# MTX_Tap_an_er_V152.net
KiCad netlist of a schematic drawn in EAGLE
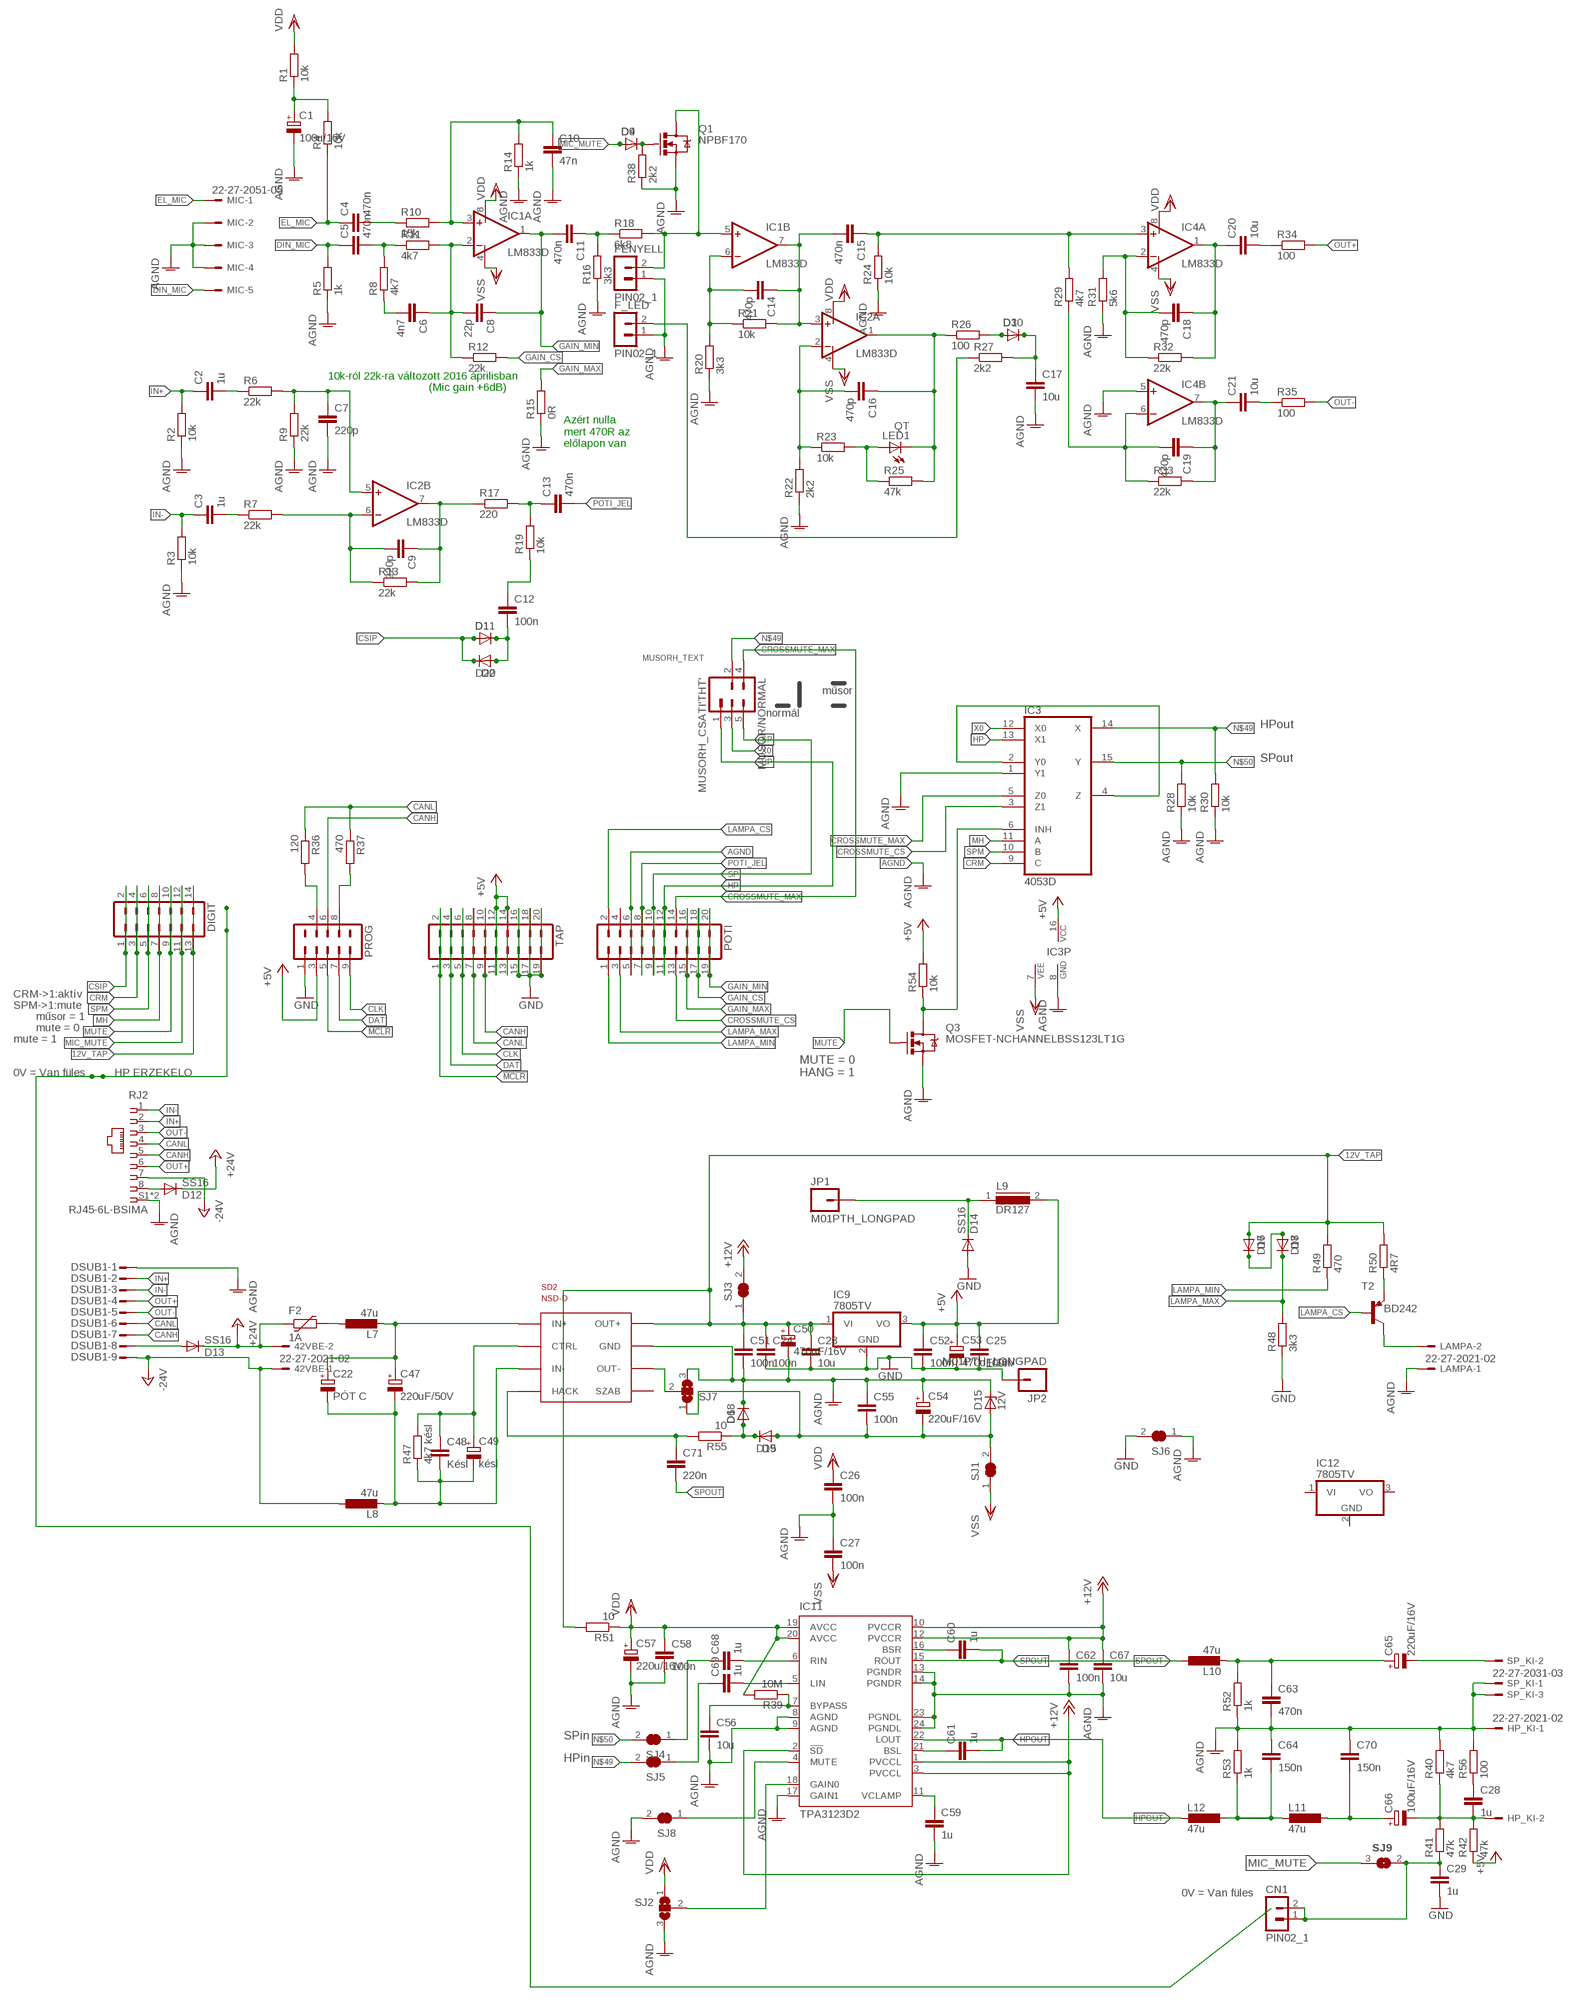
[diagram p0: schematic, sheet 1]

(export (version "E")
  (design (tool "Eeschema 10.0.6"))
  (components
    (comp (ref "42VBE")
      (value "22-27-2021-02")
      (footprint "eagle-import:6410-02")
      (libsource (lib "eagle-import") (part "22-?-0227-2021"))
    )
    (comp (ref "C1")
      (value "100u/16V")
      (footprint "eagle-import:E2,5-5")
      (libsource (lib "eagle-import") (part "CPOL-EUE2.5-5"))
    )
    (comp (ref "C2")
      (value "1u")
      (footprint "eagle-import:C0805")
      (libsource (lib "eagle-import") (part "C-EUC0805"))
    )
    (comp (ref "C3")
      (value "1u")
      (footprint "eagle-import:C0805")
      (libsource (lib "eagle-import") (part "C-EUC0805"))
    )
    (comp (ref "C4")
      (value "470n")
      (footprint "eagle-import:C0805")
      (libsource (lib "eagle-import") (part "C-EUC0805"))
    )
    (comp (ref "C5")
      (value "470n")
      (footprint "eagle-import:C0805")
      (libsource (lib "eagle-import") (part "C-EUC0805"))
    )
    (comp (ref "C6")
      (value "4n7")
      (footprint "eagle-import:C0805")
      (libsource (lib "eagle-import") (part "C-EUC0805"))
    )
    (comp (ref "C7")
      (value "220p")
      (footprint "eagle-import:C0805")
      (libsource (lib "eagle-import") (part "C-EUC0805"))
    )
    (comp (ref "C8")
      (value "22p")
      (footprint "eagle-import:C0805")
      (libsource (lib "eagle-import") (part "C-EUC0805"))
    )
    (comp (ref "C9")
      (value "220p")
      (footprint "eagle-import:C0805")
      (libsource (lib "eagle-import") (part "C-EUC0805"))
    )
    (comp (ref "C10")
      (value "47n")
      (footprint "eagle-import:C0805")
      (libsource (lib "eagle-import") (part "C-EUC0805"))
    )
    (comp (ref "C11")
      (value "470n")
      (footprint "eagle-import:C0805")
      (libsource (lib "eagle-import") (part "C-EUC0805"))
    )
    (comp (ref "C12")
      (value "100n")
      (footprint "eagle-import:C0805")
      (libsource (lib "eagle-import") (part "C-EUC0805"))
    )
    (comp (ref "C13")
      (value "470n")
      (footprint "eagle-import:C0805")
      (libsource (lib "eagle-import") (part "C-EUC0805"))
    )
    (comp (ref "C14")
      (value "470p")
      (footprint "eagle-import:C0805")
      (libsource (lib "eagle-import") (part "C-EUC0805"))
    )
    (comp (ref "C15")
      (value "470n")
      (footprint "eagle-import:C0805")
      (libsource (lib "eagle-import") (part "C-EUC0805"))
    )
    (comp (ref "C16")
      (value "470p")
      (footprint "eagle-import:C0805")
      (libsource (lib "eagle-import") (part "C-EUC0805"))
    )
    (comp (ref "C17")
      (value "10u")
      (footprint "eagle-import:C0805")
      (libsource (lib "eagle-import") (part "C-EUC0805"))
    )
    (comp (ref "C18")
      (value "470p")
      (footprint "eagle-import:C0805")
      (libsource (lib "eagle-import") (part "C-EUC0805"))
    )
    (comp (ref "C19")
      (value "470p")
      (footprint "eagle-import:C0805")
      (libsource (lib "eagle-import") (part "C-EUC0805"))
    )
    (comp (ref "C20")
      (value "10u")
      (footprint "eagle-import:C0805")
      (libsource (lib "eagle-import") (part "C-EUC0805"))
    )
    (comp (ref "C21")
      (value "10u")
      (footprint "eagle-import:C0805")
      (libsource (lib "eagle-import") (part "C-EUC0805"))
    )
    (comp (ref "C22")
      (value "PÓT C")
      (footprint "eagle-import:E3,5-8")
      (libsource (lib "eagle-import") (part "CPOL-EUE3.5-8"))
    )
    (comp (ref "C23")
      (value "10u")
      (footprint "eagle-import:C0805")
      (libsource (lib "eagle-import") (part "C-EUC0805"))
    )
    (comp (ref "C24")
      (value "100n")
      (footprint "eagle-import:C0805")
      (libsource (lib "eagle-import") (part "C-EUC0805"))
    )
    (comp (ref "C25")
      (value "100n")
      (footprint "eagle-import:C0805")
      (libsource (lib "eagle-import") (part "C-EUC0805"))
    )
    (comp (ref "C26")
      (value "100n")
      (footprint "eagle-import:C0805")
      (libsource (lib "eagle-import") (part "C-EUC0805"))
    )
    (comp (ref "C27")
      (value "100n")
      (footprint "eagle-import:C0805")
      (libsource (lib "eagle-import") (part "C-EUC0805"))
    )
    (comp (ref "C28")
      (value "1u")
      (footprint "eagle-import:C0805")
      (libsource (lib "eagle-import") (part "C-EUC0805"))
    )
    (comp (ref "C29")
      (value "1u")
      (footprint "eagle-import:C0805")
      (libsource (lib "eagle-import") (part "C-EUC0805"))
    )
    (comp (ref "C47")
      (value "220uF/50V")
      (footprint "eagle-import:E3,5-8")
      (libsource (lib "eagle-import") (part "CPOL-EUE3.5-8"))
    )
    (comp (ref "C48")
      (value "Késl")
      (footprint "eagle-import:C0805")
      (libsource (lib "eagle-import") (part "C-EUC0805"))
    )
    (comp (ref "C49")
      (value "késl")
      (footprint "eagle-import:E2,5-5")
      (libsource (lib "eagle-import") (part "CPOL-EUE2.5-5"))
    )
    (comp (ref "C50")
      (value "470uF/16V")
      (footprint "eagle-import:E3,5-8")
      (libsource (lib "eagle-import") (part "CPOL-EUE3.5-8"))
    )
    (comp (ref "C51")
      (value "100n")
      (footprint "eagle-import:C0805")
      (libsource (lib "eagle-import") (part "C-EUC0805"))
    )
    (comp (ref "C52")
      (value "100n")
      (footprint "eagle-import:C0805")
      (libsource (lib "eagle-import") (part "C-EUC0805"))
    )
    (comp (ref "C53")
      (value "470uF/16V")
      (footprint "eagle-import:E3,5-8")
      (libsource (lib "eagle-import") (part "CPOL-EUE3.5-8"))
    )
    (comp (ref "C54")
      (value "220uF/16V")
      (footprint "eagle-import:E2,5-7")
      (libsource (lib "eagle-import") (part "CPOL-EUE2.5-7"))
    )
    (comp (ref "C55")
      (value "100n")
      (footprint "eagle-import:C0805")
      (libsource (lib "eagle-import") (part "C-EUC0805"))
    )
    (comp (ref "C56")
      (value "10u")
      (footprint "eagle-import:C0805")
      (libsource (lib "eagle-import") (part "C-EUC0805"))
    )
    (comp (ref "C57")
      (value "220u/16V")
      (footprint "eagle-import:E2,5-7")
      (libsource (lib "eagle-import") (part "CPOL-EUE2.5-7"))
    )
    (comp (ref "C58")
      (value "100n")
      (footprint "eagle-import:C0805")
      (libsource (lib "eagle-import") (part "C-EUC0805"))
    )
    (comp (ref "C59")
      (value "1u")
      (footprint "eagle-import:C0805")
      (libsource (lib "eagle-import") (part "C-EUC0805"))
    )
    (comp (ref "C60")
      (value "1u")
      (footprint "eagle-import:C0805")
      (libsource (lib "eagle-import") (part "C-EUC0805"))
    )
    (comp (ref "C61")
      (value "1u")
      (footprint "eagle-import:C0805")
      (libsource (lib "eagle-import") (part "C-EUC0805"))
    )
    (comp (ref "C62")
      (value "100n")
      (footprint "eagle-import:C0805")
      (libsource (lib "eagle-import") (part "C-EUC0805"))
    )
    (comp (ref "C63")
      (value "470n")
      (footprint "eagle-import:C0805")
      (libsource (lib "eagle-import") (part "C-EUC0805"))
    )
    (comp (ref "C64")
      (value "150n")
      (footprint "eagle-import:C0805")
      (libsource (lib "eagle-import") (part "C-EUC0805"))
    )
    (comp (ref "C65")
      (value "220uF/16V")
      (footprint "eagle-import:E2,5-7")
      (libsource (lib "eagle-import") (part "CPOL-EUE2.5-7"))
    )
    (comp (ref "C66")
      (value "100uF/16V")
      (footprint "eagle-import:E2,5-6")
      (libsource (lib "eagle-import") (part "CPOL-EUE2.5-6"))
    )
    (comp (ref "C67")
      (value "10u")
      (footprint "eagle-import:C0805")
      (libsource (lib "eagle-import") (part "C-EUC0805"))
    )
    (comp (ref "C68")
      (value "1u")
      (footprint "eagle-import:C0805")
      (libsource (lib "eagle-import") (part "C-EUC0805"))
    )
    (comp (ref "C69")
      (value "1u")
      (footprint "eagle-import:C0805")
      (libsource (lib "eagle-import") (part "C-EUC0805"))
    )
    (comp (ref "C70")
      (value "150n")
      (footprint "eagle-import:C0805")
      (libsource (lib "eagle-import") (part "C-EUC0805"))
    )
    (comp (ref "C71")
      (value "220n")
      (footprint "eagle-import:C0805")
      (libsource (lib "eagle-import") (part "C-EUC0805"))
    )
    (comp (ref "CN1")
      (value "PIN02_1")
      (footprint "eagle-import:PIN02_1")
      (libsource (lib "eagle-import") (part "PIN02_1"))
    )
    (comp (ref "D1")
      (value "1N4148")
      (footprint "eagle-import:DGLASSSMD")
      (libsource (lib "eagle-import") (part "DGLASSMD"))
    )
    (comp (ref "D2")
      (value "1N4148")
      (footprint "eagle-import:DGLASSSMD")
      (libsource (lib "eagle-import") (part "DGLASSMD"))
    )
    (comp (ref "D3")
      (value "1N4148")
      (footprint "eagle-import:DGLASSSMD")
      (libsource (lib "eagle-import") (part "DGLASSMD"))
    )
    (comp (ref "D4")
      (value "1N4148")
      (footprint "eagle-import:DGLASSSMD")
      (libsource (lib "eagle-import") (part "DGLASSMD"))
    )
    (comp (ref "D5")
      (value "D0805")
      (footprint "eagle-import:D0805")
      (libsource (lib "eagle-import") (part "D0805"))
    )
    (comp (ref "D6")
      (value "D0805")
      (footprint "eagle-import:D0805")
      (libsource (lib "eagle-import") (part "D0805"))
    )
    (comp (ref "D7")
      (value "D0805")
      (footprint "eagle-import:D0805")
      (libsource (lib "eagle-import") (part "D0805"))
    )
    (comp (ref "D8")
      (value "D0805")
      (footprint "eagle-import:D0805")
      (libsource (lib "eagle-import") (part "D0805"))
    )
    (comp (ref "D9")
      (value "D0805")
      (footprint "eagle-import:D0805")
      (libsource (lib "eagle-import") (part "D0805"))
    )
    (comp (ref "D10")
      (value "D0805")
      (footprint "eagle-import:D0805")
      (libsource (lib "eagle-import") (part "D0805"))
    )
    (comp (ref "D11")
      (value "D0805")
      (footprint "eagle-import:D0805")
      (libsource (lib "eagle-import") (part "D0805"))
    )
    (comp (ref "D12")
      (value "SS16")
      (footprint "eagle-import:DO-214AC")
      (libsource (lib "eagle-import") (part "SS16"))
    )
    (comp (ref "D13")
      (value "SS16")
      (footprint "eagle-import:DO-214AC")
      (libsource (lib "eagle-import") (part "SS16"))
    )
    (comp (ref "D14")
      (value "SS16")
      (footprint "eagle-import:DO-214AC")
      (libsource (lib "eagle-import") (part "DIODE-DO-214AC"))
    )
    (comp (ref "D15")
      (value "12V")
      (footprint "eagle-import:SOD80C")
      (libsource (lib "eagle-import") (part "ZENER-DIODESOD80C"))
    )
    (comp (ref "D16")
      (value "1N4148")
      (footprint "eagle-import:DGLASSSMD")
      (libsource (lib "eagle-import") (part "DGLASSMD"))
    )
    (comp (ref "D17")
      (value "1N4148")
      (footprint "eagle-import:DGLASSSMD")
      (libsource (lib "eagle-import") (part "DGLASSMD"))
    )
    (comp (ref "D18")
      (value "1N4148")
      (footprint "eagle-import:DGLASSSMD")
      (libsource (lib "eagle-import") (part "DGLASSMD"))
    )
    (comp (ref "D19")
      (value "1N4148")
      (footprint "eagle-import:DGLASSSMD")
      (libsource (lib "eagle-import") (part "DGLASSMD"))
    )
    (comp (ref "D20")
      (value "D0805")
      (footprint "eagle-import:D0805")
      (libsource (lib "eagle-import") (part "D0805"))
    )
    (comp (ref "DIGIT")
      (value "MA07-2")
      (footprint "eagle-import:MA07-2")
      (libsource (lib "eagle-import") (part "MA07-2"))
    )
    (comp (ref "DSUB1")
      (value "M09-182S")
      (footprint "eagle-import:182-009-MALE")
      (libsource (lib "eagle-import") (part "M09?S-182"))
    )
    (comp (ref "F2")
      (value "1A")
      (footprint "eagle-import:PTC1812L")
      (libsource (lib "eagle-import") (part "FUSE_PTC-1812"))
    )
    (comp (ref "FENYELL")
      (value "PIN02_1")
      (footprint "eagle-import:PIN02_1")
      (libsource (lib "eagle-import") (part "PIN02_1"))
    )
    (comp (ref "F_LED")
      (value "PIN02_1")
      (footprint "eagle-import:PIN02_1")
      (libsource (lib "eagle-import") (part "PIN02_1"))
    )
    (comp (ref "HP_KI")
      (value "22-27-2021-02")
      (footprint "eagle-import:6410-02")
      (libsource (lib "eagle-import") (part "22-?-0227-2021"))
    )
    (comp (ref "IC1")
      (value "LM833D")
      (footprint "eagle-import:SO08")
      (libsource (lib "eagle-import") (part "LM833D"))
    )
    (comp (ref "IC2")
      (value "LM833D")
      (footprint "eagle-import:SO08")
      (libsource (lib "eagle-import") (part "LM833D"))
    )
    (comp (ref "IC3")
      (value "4053D")
      (footprint "eagle-import:SO16")
      (libsource (lib "eagle-import") (part "4053D"))
    )
    (comp (ref "IC4")
      (value "LM833D")
      (footprint "eagle-import:SO08")
      (libsource (lib "eagle-import") (part "LM833D"))
    )
    (comp (ref "IC9")
      (value "7805TV")
      (footprint "eagle-import:TO220V")
      (libsource (lib "eagle-import") (part "78TV05"))
    )
    (comp (ref "IC11")
      (value "TPA3123D2")
      (footprint "eagle-import:PWP-TSSOP24")
      (fields (field (name "MPN") "TPA3123D2PWP"))
      (libsource (lib "eagle-import") (part "TPA3123D2"))
    )
    (comp (ref "IC12")
      (value "7805TV")
      (footprint "eagle-import:TO220V")
      (libsource (lib "eagle-import") (part "78TV05"))
    )
    (comp (ref "JP1")
      (value "M01PTH_LONGPAD")
      (footprint "eagle-import:1X01_LONGPAD")
      (libsource (lib "eagle-import") (part "M01PTH_LONGPAD"))
    )
    (comp (ref "JP2")
      (value "M01PTH_LONGPAD")
      (footprint "eagle-import:1X01_LONGPAD")
      (libsource (lib "eagle-import") (part "M01PTH_LONGPAD"))
    )
    (comp (ref "L7")
      (value "47u")
      (footprint "eagle-import:PIS2816")
      (libsource (lib "eagle-import") (part "L-EUPIS2816"))
    )
    (comp (ref "L8")
      (value "47u")
      (footprint "eagle-import:PIS2816")
      (libsource (lib "eagle-import") (part "L-EUPIS2816"))
    )
    (comp (ref "L9")
      (value "DR127")
      (footprint "eagle-import:DR127")
      (libsource (lib "eagle-import") (part "DR127"))
    )
    (comp (ref "L10")
      (value "47u")
      (footprint "eagle-import:PIS2816")
      (libsource (lib "eagle-import") (part "L-EUPIS2816"))
    )
    (comp (ref "L11")
      (value "47u")
      (footprint "eagle-import:PIS2816")
      (libsource (lib "eagle-import") (part "L-EUPIS2816"))
    )
    (comp (ref "L12")
      (value "47u")
      (footprint "eagle-import:PIS2816")
      (libsource (lib "eagle-import") (part "L-EUPIS2816"))
    )
    (comp (ref "LAMPA")
      (value "22-27-2021-02")
      (footprint "eagle-import:6410-02")
      (libsource (lib "eagle-import") (part "22-?-0227-2021"))
    )
    (comp (ref "LED1")
      (value "QT")
      (footprint "eagle-import:LED3MM")
      (libsource (lib "eagle-import") (part "LED3MM"))
    )
    (comp (ref "MIC")
      (value "22-27-2051-05")
      (footprint "eagle-import:6410-05")
      (libsource (lib "eagle-import") (part "22-?-0527-2051"))
    )
    (comp (ref "MUSOR/NORMAL")
      (value "MUSORH_CSATI'THT'")
      (footprint "eagle-import:MUSORH_CSATI")
      (libsource (lib "eagle-import") (part "MUSORH_CSATI'THT'"))
    )
    (comp (ref "POTI")
      (value "MA10-2")
      (footprint "eagle-import:MA10-2")
      (libsource (lib "eagle-import") (part "MA10-2"))
    )
    (comp (ref "PROG")
      (value "CN_CANTAN")
      (footprint "eagle-import:CN_CANTAN")
      (libsource (lib "eagle-import") (part "CN_CANTAN"))
    )
    (comp (ref "Q1")
      (value "NPBF170")
      (footprint "eagle-import:SOT23")
      (libsource (lib "eagle-import") (part "MOSFET-NCHANNELBSS138"))
    )
    (comp (ref "Q3")
      (value "MOSFET-NCHANNELBSS123LT1G")
      (footprint "eagle-import:SOT23")
      (libsource (lib "eagle-import") (part "MOSFET-NCHANNELBSS123LT1G"))
    )
    (comp (ref "R1")
      (value "10k")
      (footprint "eagle-import:R0805")
      (libsource (lib "eagle-import") (part "R-EU_R0805"))
    )
    (comp (ref "R2")
      (value "10k")
      (footprint "eagle-import:R0805")
      (libsource (lib "eagle-import") (part "R-EU_R0805"))
    )
    (comp (ref "R3")
      (value "10k")
      (footprint "eagle-import:R0805")
      (libsource (lib "eagle-import") (part "R-EU_R0805"))
    )
    (comp (ref "R4")
      (value "10k")
      (footprint "eagle-import:R0805")
      (libsource (lib "eagle-import") (part "R-EU_R0805"))
    )
    (comp (ref "R5")
      (value "1k")
      (footprint "eagle-import:R0805")
      (libsource (lib "eagle-import") (part "R-EU_R0805"))
    )
    (comp (ref "R6")
      (value "22k")
      (footprint "eagle-import:R0805")
      (libsource (lib "eagle-import") (part "R-EU_R0805"))
    )
    (comp (ref "R7")
      (value "22k")
      (footprint "eagle-import:R0805")
      (libsource (lib "eagle-import") (part "R-EU_R0805"))
    )
    (comp (ref "R8")
      (value "4k7")
      (footprint "eagle-import:R0805")
      (libsource (lib "eagle-import") (part "R-EU_R0805"))
    )
    (comp (ref "R9")
      (value "22k")
      (footprint "eagle-import:R0805")
      (libsource (lib "eagle-import") (part "R-EU_R0805"))
    )
    (comp (ref "R10")
      (value "15k")
      (footprint "eagle-import:R0805")
      (libsource (lib "eagle-import") (part "R-EU_R0805"))
    )
    (comp (ref "R11")
      (value "4k7")
      (footprint "eagle-import:R0805")
      (libsource (lib "eagle-import") (part "R-EU_R0805"))
    )
    (comp (ref "R12")
      (value "22k")
      (footprint "eagle-import:R0805")
      (libsource (lib "eagle-import") (part "R-EU_R0805"))
    )
    (comp (ref "R13")
      (value "22k")
      (footprint "eagle-import:R0805")
      (libsource (lib "eagle-import") (part "R-EU_R0805"))
    )
    (comp (ref "R14")
      (value "1k")
      (footprint "eagle-import:R0805")
      (libsource (lib "eagle-import") (part "R-EU_R0805"))
    )
    (comp (ref "R15")
      (value "0R")
      (footprint "eagle-import:R0805")
      (libsource (lib "eagle-import") (part "R-EU_R0805"))
    )
    (comp (ref "R16")
      (value "3k3")
      (footprint "eagle-import:R0805")
      (libsource (lib "eagle-import") (part "R-EU_R0805"))
    )
    (comp (ref "R17")
      (value "220")
      (footprint "eagle-import:R0805")
      (libsource (lib "eagle-import") (part "R-EU_R0805"))
    )
    (comp (ref "R18")
      (value "6k8")
      (footprint "eagle-import:R0805")
      (libsource (lib "eagle-import") (part "R-EU_R0805"))
    )
    (comp (ref "R19")
      (value "10k")
      (footprint "eagle-import:R0805")
      (libsource (lib "eagle-import") (part "R-EU_R0805"))
    )
    (comp (ref "R20")
      (value "3k3")
      (footprint "eagle-import:R0805")
      (libsource (lib "eagle-import") (part "R-EU_R0805"))
    )
    (comp (ref "R21")
      (value "10k")
      (footprint "eagle-import:R0805")
      (libsource (lib "eagle-import") (part "R-EU_R0805"))
    )
    (comp (ref "R22")
      (value "2k2")
      (footprint "eagle-import:R0805")
      (libsource (lib "eagle-import") (part "R-EU_R0805"))
    )
    (comp (ref "R23")
      (value "10k")
      (footprint "eagle-import:R0805")
      (libsource (lib "eagle-import") (part "R-EU_R0805"))
    )
    (comp (ref "R24")
      (value "10k")
      (footprint "eagle-import:R0805")
      (libsource (lib "eagle-import") (part "R-EU_R0805"))
    )
    (comp (ref "R25")
      (value "47k")
      (footprint "eagle-import:R0805")
      (libsource (lib "eagle-import") (part "R-EU_R0805"))
    )
    (comp (ref "R26")
      (value "100")
      (footprint "eagle-import:R0805")
      (libsource (lib "eagle-import") (part "R-EU_R0805"))
    )
    (comp (ref "R27")
      (value "2k2")
      (footprint "eagle-import:R0805")
      (libsource (lib "eagle-import") (part "R-EU_R0805"))
    )
    (comp (ref "R28")
      (value "10k")
      (footprint "eagle-import:R0805")
      (libsource (lib "eagle-import") (part "R-EU_R0805"))
    )
    (comp (ref "R29")
      (value "4k7")
      (footprint "eagle-import:R0805")
      (libsource (lib "eagle-import") (part "R-EU_R0805"))
    )
    (comp (ref "R30")
      (value "10k")
      (footprint "eagle-import:R0805")
      (libsource (lib "eagle-import") (part "R-EU_R0805"))
    )
    (comp (ref "R31")
      (value "5k6")
      (footprint "eagle-import:R0805")
      (libsource (lib "eagle-import") (part "R-EU_R0805"))
    )
    (comp (ref "R32")
      (value "22k")
      (footprint "eagle-import:R0805")
      (libsource (lib "eagle-import") (part "R-EU_R0805"))
    )
    (comp (ref "R33")
      (value "22k")
      (footprint "eagle-import:R0805")
      (libsource (lib "eagle-import") (part "R-EU_R0805"))
    )
    (comp (ref "R34")
      (value "100")
      (footprint "eagle-import:R0805")
      (libsource (lib "eagle-import") (part "R-EU_R0805"))
    )
    (comp (ref "R35")
      (value "100")
      (footprint "eagle-import:R0805")
      (libsource (lib "eagle-import") (part "R-EU_R0805"))
    )
    (comp (ref "R36")
      (value "120")
      (footprint "eagle-import:R0805")
      (libsource (lib "eagle-import") (part "R-EU_R0805"))
    )
    (comp (ref "R37")
      (value "470")
      (footprint "eagle-import:R0805")
      (libsource (lib "eagle-import") (part "R-EU_R0805"))
    )
    (comp (ref "R38")
      (value "2k2")
      (footprint "eagle-import:R0805")
      (libsource (lib "eagle-import") (part "R-EU_R0805"))
    )
    (comp (ref "R39")
      (value "10M")
      (footprint "eagle-import:R0805")
      (libsource (lib "eagle-import") (part "R-EU_R0805"))
    )
    (comp (ref "R40")
      (value "4k7")
      (footprint "eagle-import:R0805")
      (libsource (lib "eagle-import") (part "R-EU_R0805"))
    )
    (comp (ref "R41")
      (value "47k")
      (footprint "eagle-import:R0805")
      (libsource (lib "eagle-import") (part "R-EU_R0805"))
    )
    (comp (ref "R42")
      (value "47k")
      (footprint "eagle-import:R0805")
      (libsource (lib "eagle-import") (part "R-EU_R0805"))
    )
    (comp (ref "R47")
      (value "4k7 késl")
      (footprint "eagle-import:R0805")
      (libsource (lib "eagle-import") (part "R-EU_R0805"))
    )
    (comp (ref "R48")
      (value "3k3")
      (footprint "eagle-import:R0805")
      (libsource (lib "eagle-import") (part "R-EU_R0805"))
    )
    (comp (ref "R49")
      (value "470")
      (footprint "eagle-import:R0805")
      (libsource (lib "eagle-import") (part "R-EU_R0805"))
    )
    (comp (ref "R50")
      (value "4R7")
      (footprint "eagle-import:R0805")
      (libsource (lib "eagle-import") (part "R-EU_R0805"))
    )
    (comp (ref "R51")
      (value "10")
      (footprint "eagle-import:R1210")
      (libsource (lib "eagle-import") (part "R-EU_R1210"))
    )
    (comp (ref "R52")
      (value "1k")
      (footprint "eagle-import:R0805")
      (libsource (lib "eagle-import") (part "R-EU_R0805"))
    )
    (comp (ref "R53")
      (value "1k")
      (footprint "eagle-import:R0805")
      (libsource (lib "eagle-import") (part "R-EU_R0805"))
    )
    (comp (ref "R54")
      (value "10k")
      (footprint "eagle-import:R0805")
      (libsource (lib "eagle-import") (part "R-EU_R0805"))
    )
    (comp (ref "R55")
      (value "10")
      (footprint "eagle-import:R0805")
      (libsource (lib "eagle-import") (part "R-EU_R0805"))
    )
    (comp (ref "R56")
      (value "100")
      (footprint "eagle-import:R0805")
      (libsource (lib "eagle-import") (part "R-EU_R0805"))
    )
    (comp (ref "RJ2")
      (value "RJ45-6L-BSIMA")
      (footprint "eagle-import:RJ45")
      (fields (field (name "MPN") "RJ45-6L-B"))
      (libsource (lib "eagle-import") (part "RJ45SIMA-6L-B"))
    )
    (comp (ref "SD2")
      (value "NSD-D")
      (footprint "eagle-import:NSD-D")
      (libsource (lib "eagle-import") (part "NSD-D"))
    )
    (comp (ref "SJ1")
      (value "SOLDERJUMPER_CLOSED")
      (footprint "eagle-import:SOLDERJUMPER_CLOSEDWIRE")
      (libsource (lib "eagle-import") (part "SOLDERJUMPER_CLOSED"))
    )
    (comp (ref "SJ2")
      (value "SJ2WW12")
      (footprint "eagle-import:SJ_2W_12")
      (libsource (lib "eagle-import") (part "SJ2WW12"))
    )
    (comp (ref "SJ3")
      (value "SOLDERJUMPER_CLOSED")
      (footprint "eagle-import:SOLDERJUMPER_CLOSEDWIRE")
      (libsource (lib "eagle-import") (part "SOLDERJUMPER_CLOSED"))
    )
    (comp (ref "SJ4")
      (value "SOLDERJUMPER_CLOSED")
      (footprint "eagle-import:SOLDERJUMPER_CLOSEDWIRE")
      (libsource (lib "eagle-import") (part "SOLDERJUMPER_CLOSED"))
    )
    (comp (ref "SJ5")
      (value "SOLDERJUMPER_CLOSED")
      (footprint "eagle-import:SOLDERJUMPER_CLOSEDWIRE")
      (libsource (lib "eagle-import") (part "SOLDERJUMPER_CLOSED"))
    )
    (comp (ref "SJ6")
      (value "SOLDERJUMPER_CLOSED")
      (footprint "eagle-import:SOLDERJUMPER_CLOSEDWIRE")
      (libsource (lib "eagle-import") (part "SOLDERJUMPER_CLOSED"))
    )
    (comp (ref "SJ7")
      (value "SJ2WW23")
      (footprint "eagle-import:SJ_2W_23")
      (libsource (lib "eagle-import") (part "SJ2WW23"))
    )
    (comp (ref "SJ8")
      (value "SOLDERJUMPER_CLOSED")
      (footprint "eagle-import:SOLDERJUMPER_CLOSEDWIRE")
      (libsource (lib "eagle-import") (part "SOLDERJUMPER_CLOSED"))
    )
    (comp (ref "SJ9") (value "SJ") (footprint "eagle-import:SJ") (libsource (lib "eagle-import") (part "SJ")))
    (comp (ref "SP_KI")
      (value "22-27-2031-03")
      (footprint "eagle-import:6410-03")
      (libsource (lib "eagle-import") (part "22-?-0327-2031"))
    )
    (comp (ref "T2")
      (value "BD242")
      (footprint "eagle-import:TO220V")
      (libsource (lib "eagle-import") (part "-PNP-TO220V"))
    )
    (comp (ref "TAP")
      (value "MA10-2")
      (footprint "eagle-import:MA10-2")
      (libsource (lib "eagle-import") (part "MA10-2"))
    )
    (comp (ref "U$1")
      (value "MUSORH_TEXT")
      (footprint "eagle-import:MUSORH_TEXT")
      (libsource (lib "eagle-import") (part "MUSORH_TEXT"))
    )
  )
  (nets
    (net (code "1") (name "+5V") (class "Default")
      (node (ref "C25") (pin "1") (pinfunction "1_1") (pintype "passive"))
      (node (ref "C52") (pin "1") (pinfunction "1_1") (pintype "passive"))
      (node (ref "C53") (pin "+") (pinfunction "+_+") (pintype "passive"))
      (node (ref "IC3") (pin "16") (pinfunction "VCC_16") (pintype "power_in"))
      (node (ref "IC9") (pin "3") (pinfunction "VO_3") (pintype "passive"))
      (node (ref "L9") (pin "2") (pinfunction "2_2") (pintype "passive"))
      (node (ref "PROG") (pin "3") (pinfunction "3_3") (pintype "passive"))
      (node (ref "R42") (pin "1") (pinfunction "1_1") (pintype "passive"))
      (node (ref "R54") (pin "2") (pinfunction "2_2") (pintype "passive"))
      (node (ref "TAP") (pin "11") (pinfunction "11_11") (pintype "passive"))
      (node (ref "TAP") (pin "12") (pinfunction "12_12") (pintype "passive"))
      (node (ref "TAP") (pin "13") (pinfunction "13_13") (pintype "passive"))
      (node (ref "TAP") (pin "14") (pinfunction "14_14") (pintype "passive"))
    )
    (net (code "2") (name "+12V") (class "Default")
      (node (ref "C62") (pin "1") (pinfunction "1_1") (pintype "passive"))
      (node (ref "C67") (pin "1") (pinfunction "1_1") (pintype "passive"))
      (node (ref "IC11") (pin "1") (pinfunction "PVCCL_1") (pintype "input"))
      (node (ref "IC11") (pin "10") (pinfunction "PVCCR_10") (pintype "input"))
      (node (ref "IC11") (pin "12") (pinfunction "PVCCR_12") (pintype "input"))
      (node (ref "IC11") (pin "2") (pinfunction "~{SD}_2") (pintype "input"))
      (node (ref "IC11") (pin "3") (pinfunction "PVCCL_3") (pintype "input"))
      (node (ref "SJ3") (pin "2") (pinfunction "2_2") (pintype "passive"))
    )
    (net (code "3") (name "+24V") (class "Default")
      (node (ref "42VBE") (pin "2") (pinfunction "S_2") (pintype "passive"))
      (node (ref "D12") (pin "1") (pinfunction "C_1") (pintype "passive"))
      (node (ref "D13") (pin "1") (pinfunction "C_1") (pintype "passive"))
      (node (ref "F2") (pin "1") (pinfunction "1_1") (pintype "passive"))
    )
    (net (code "4") (name "-24V") (class "Default")
      (node (ref "42VBE") (pin "1") (pinfunction "S_1") (pintype "passive"))
      (node (ref "DSUB1") (pin "9") (pinfunction "M_9") (pintype "passive"))
      (node (ref "L8") (pin "1") (pinfunction "1_1") (pintype "passive"))
      (node (ref "RJ2") (pin "7") (pinfunction "7_7") (pintype "passive"))
    )
    (net (code "5") (name "/~{MCLR}") (class "Default")
      (node (ref "PROG") (pin "5") (pinfunction "5_5") (pintype "passive"))
      (node (ref "TAP") (pin "1") (pinfunction "1_1") (pintype "passive"))
      (node (ref "TAP") (pin "2") (pinfunction "2_2") (pintype "passive"))
    )
    (net (code "6") (name "12V_TAP") (class "Default")
      (node (ref "C23") (pin "1") (pinfunction "1_1") (pintype "passive"))
      (node (ref "C24") (pin "1") (pinfunction "1_1") (pintype "passive"))
      (node (ref "C50") (pin "+") (pinfunction "+_+") (pintype "passive"))
      (node (ref "C51") (pin "1") (pinfunction "1_1") (pintype "passive"))
      (node (ref "D16") (pin "P$1") (pinfunction "A_P$1") (pintype "passive"))
      (node (ref "D7") (pin "1") (pinfunction "A_1") (pintype "passive"))
      (node (ref "DIGIT") (pin "13") (pinfunction "13_13") (pintype "passive"))
      (node (ref "DIGIT") (pin "14") (pinfunction "14_14") (pintype "passive"))
      (node (ref "IC9") (pin "1") (pinfunction "VI_1") (pintype "input"))
      (node (ref "R49") (pin "2") (pinfunction "2_2") (pintype "passive"))
      (node (ref "R50") (pin "2") (pinfunction "2_2") (pintype "passive"))
      (node (ref "R51") (pin "2") (pinfunction "2_2") (pintype "passive"))
      (node (ref "SD2") (pin "OUT+") (pinfunction "OUT+_OUT+") (pintype "bidirectional"))
      (node (ref "SJ3") (pin "1") (pinfunction "1_1") (pintype "passive"))
    )
    (net (code "7") (name "AGND") (class "Default")
      (node (ref "C1") (pin "-") (pinfunction "-_-") (pintype "passive"))
      (node (ref "C10") (pin "2") (pinfunction "2_2") (pintype "passive"))
      (node (ref "C17") (pin "2") (pinfunction "2_2") (pintype "passive"))
      (node (ref "C26") (pin "2") (pinfunction "2_2") (pintype "passive"))
      (node (ref "C27") (pin "1") (pinfunction "1_1") (pintype "passive"))
      (node (ref "C50") (pin "-") (pinfunction "-_-") (pintype "passive"))
      (node (ref "C51") (pin "2") (pinfunction "2_2") (pintype "passive"))
      (node (ref "C54") (pin "+") (pinfunction "+_+") (pintype "passive"))
      (node (ref "C55") (pin "1") (pinfunction "1_1") (pintype "passive"))
      (node (ref "C56") (pin "2") (pinfunction "2_2") (pintype "passive"))
      (node (ref "C57") (pin "-") (pinfunction "-_-") (pintype "passive"))
      (node (ref "C58") (pin "2") (pinfunction "2_2") (pintype "passive"))
      (node (ref "C59") (pin "2") (pinfunction "2_2") (pintype "passive"))
      (node (ref "C62") (pin "2") (pinfunction "2_2") (pintype "passive"))
      (node (ref "C63") (pin "2") (pinfunction "2_2") (pintype "passive"))
      (node (ref "C64") (pin "1") (pinfunction "1_1") (pintype "passive"))
      (node (ref "C67") (pin "2") (pinfunction "2_2") (pintype "passive"))
      (node (ref "C7") (pin "2") (pinfunction "2_2") (pintype "passive"))
      (node (ref "C70") (pin "1") (pinfunction "1_1") (pintype "passive"))
      (node (ref "D15") (pin "C") (pinfunction "C_C") (pintype "passive"))
      (node (ref "D18") (pin "P$2") (pinfunction "C_P$2") (pintype "passive"))
      (node (ref "D6") (pin "2") (pinfunction "C_2") (pintype "passive"))
      (node (ref "DSUB1") (pin "1") (pinfunction "M_1") (pintype "passive"))
      (node (ref "FENYELL") (pin "1") (pinfunction "1_1") (pintype "passive"))
      (node (ref "F_LED") (pin "1") (pinfunction "1_1") (pintype "passive"))
      (node (ref "HP_KI") (pin "1") (pinfunction "S_1") (pintype "passive"))
      (node (ref "IC11") (pin "13") (pinfunction "PGNDR_13") (pintype "input"))
      (node (ref "IC11") (pin "14") (pinfunction "PGNDR_14") (pintype "input"))
      (node (ref "IC11") (pin "17") (pinfunction "GAIN1_17") (pintype "input"))
      (node (ref "IC11") (pin "23") (pinfunction "PGNDL_23") (pintype "input"))
      (node (ref "IC11") (pin "24") (pinfunction "PGNDL_24") (pintype "input"))
      (node (ref "IC11") (pin "8") (pinfunction "AGND_8") (pintype "input"))
      (node (ref "IC11") (pin "9") (pinfunction "AGND_9") (pintype "input"))
      (node (ref "IC3") (pin "1") (pinfunction "Y1_1") (pintype "bidirectional"))
      (node (ref "IC3") (pin "8") (pinfunction "GND_8") (pintype "power_in"))
      (node (ref "IC4") (pin "5") (pinfunction "+IN_5") (pintype "input"))
      (node (ref "LAMPA") (pin "1") (pinfunction "S_1") (pintype "passive"))
      (node (ref "MIC") (pin "2") (pinfunction "S_2") (pintype "passive"))
      (node (ref "MIC") (pin "3") (pinfunction "S_3") (pintype "passive"))
      (node (ref "MIC") (pin "4") (pinfunction "S_4") (pintype "passive"))
      (node (ref "POTI") (pin "5") (pinfunction "5_5") (pintype "passive"))
      (node (ref "POTI") (pin "6") (pinfunction "6_6") (pintype "passive"))
      (node (ref "Q1") (pin "2") (pinfunction "S_2") (pintype "passive"))
      (node (ref "Q3") (pin "2") (pinfunction "S_2") (pintype "passive"))
      (node (ref "R14") (pin "1") (pinfunction "1_1") (pintype "passive"))
      (node (ref "R15") (pin "1") (pinfunction "1_1") (pintype "passive"))
      (node (ref "R16") (pin "1") (pinfunction "1_1") (pintype "passive"))
      (node (ref "R2") (pin "1") (pinfunction "1_1") (pintype "passive"))
      (node (ref "R20") (pin "1") (pinfunction "1_1") (pintype "passive"))
      (node (ref "R22") (pin "1") (pinfunction "1_1") (pintype "passive"))
      (node (ref "R24") (pin "1") (pinfunction "1_1") (pintype "passive"))
      (node (ref "R28") (pin "1") (pinfunction "1_1") (pintype "passive"))
      (node (ref "R3") (pin "1") (pinfunction "1_1") (pintype "passive"))
      (node (ref "R30") (pin "1") (pinfunction "1_1") (pintype "passive"))
      (node (ref "R31") (pin "1") (pinfunction "1_1") (pintype "passive"))
      (node (ref "R38") (pin "1") (pinfunction "1_1") (pintype "passive"))
      (node (ref "R40") (pin "2") (pinfunction "2_2") (pintype "passive"))
      (node (ref "R5") (pin "1") (pinfunction "1_1") (pintype "passive"))
      (node (ref "R52") (pin "1") (pinfunction "1_1") (pintype "passive"))
      (node (ref "R53") (pin "2") (pinfunction "2_2") (pintype "passive"))
      (node (ref "R56") (pin "2") (pinfunction "2_2") (pintype "passive"))
      (node (ref "R9") (pin "1") (pinfunction "1_1") (pintype "passive"))
      (node (ref "RJ2") (pin "S1") (pinfunction "S_S1") (pintype "passive"))
      (node (ref "RJ2") (pin "S2") (pinfunction "S_S2") (pintype "passive"))
      (node (ref "SD2") (pin "COMMON") (pinfunction "GND_COMMON") (pintype "bidirectional"))
      (node (ref "SJ2") (pin "3") (pinfunction "3_3") (pintype "passive"))
      (node (ref "SJ6") (pin "1") (pinfunction "1_1") (pintype "passive"))
      (node (ref "SJ7") (pin "3") (pinfunction "3_3") (pintype "passive"))
      (node (ref "SJ8") (pin "2") (pinfunction "2_2") (pintype "passive"))
      (node (ref "SP_KI") (pin "1") (pinfunction "S_1") (pintype "passive"))
      (node (ref "SP_KI") (pin "3") (pinfunction "S_3") (pintype "passive"))
    )
    (net (code "8") (name "CANH") (class "Default")
      (node (ref "DSUB1") (pin "7") (pinfunction "M_7") (pintype "passive"))
      (node (ref "PROG") (pin "6") (pinfunction "6_6") (pintype "passive"))
      (node (ref "RJ2") (pin "5") (pinfunction "5_5") (pintype "passive"))
      (node (ref "TAP") (pin "10") (pinfunction "10_10") (pintype "passive"))
      (node (ref "TAP") (pin "9") (pinfunction "9_9") (pintype "passive"))
    )
    (net (code "9") (name "CANL") (class "Default")
      (node (ref "DSUB1") (pin "6") (pinfunction "M_6") (pintype "passive"))
      (node (ref "R36") (pin "1") (pinfunction "1_1") (pintype "passive"))
      (node (ref "R37") (pin "1") (pinfunction "1_1") (pintype "passive"))
      (node (ref "RJ2") (pin "4") (pinfunction "4_4") (pintype "passive"))
      (node (ref "TAP") (pin "7") (pinfunction "7_7") (pintype "passive"))
      (node (ref "TAP") (pin "8") (pinfunction "8_8") (pintype "passive"))
    )
    (net (code "10") (name "CLK") (class "Default")
      (node (ref "PROG") (pin "9") (pinfunction "9_9") (pintype "passive"))
      (node (ref "TAP") (pin "5") (pinfunction "5_5") (pintype "passive"))
      (node (ref "TAP") (pin "6") (pinfunction "6_6") (pintype "passive"))
    )
    (net (code "11") (name "CRM") (class "Default")
      (node (ref "DIGIT") (pin "3") (pinfunction "3_3") (pintype "passive"))
      (node (ref "DIGIT") (pin "4") (pinfunction "4_4") (pintype "passive"))
      (node (ref "IC3") (pin "9") (pinfunction "C_9") (pintype "input"))
    )
    (net (code "12") (name "CROSSMUTE_CS") (class "Default")
      (node (ref "IC3") (pin "3") (pinfunction "Z1_3") (pintype "bidirectional"))
      (node (ref "POTI") (pin "13") (pinfunction "13_13") (pintype "passive"))
    )
    (net (code "13") (name "CROSSMUTE_MAX") (class "Default")
      (node (ref "IC3") (pin "5") (pinfunction "Z0_5") (pintype "bidirectional"))
      (node (ref "MUSOR/NORMAL") (pin "4") (pinfunction "4_4") (pintype "passive"))
      (node (ref "POTI") (pin "14") (pinfunction "14_14") (pintype "passive"))
    )
    (net (code "14") (name "CSIP") (class "Default")
      (node (ref "D1") (pin "P$1") (pinfunction "A_P$1") (pintype "passive"))
      (node (ref "D11") (pin "1") (pinfunction "A_1") (pintype "passive"))
      (node (ref "D2") (pin "P$2") (pinfunction "C_P$2") (pintype "passive"))
      (node (ref "D20") (pin "2") (pinfunction "C_2") (pintype "passive"))
      (node (ref "DIGIT") (pin "1") (pinfunction "1_1") (pintype "passive"))
      (node (ref "DIGIT") (pin "2") (pinfunction "2_2") (pintype "passive"))
    )
    (net (code "15") (name "DAT") (class "Default")
      (node (ref "PROG") (pin "7") (pinfunction "7_7") (pintype "passive"))
      (node (ref "TAP") (pin "3") (pinfunction "3_3") (pintype "passive"))
      (node (ref "TAP") (pin "4") (pinfunction "4_4") (pintype "passive"))
    )
    (net (code "16") (name "DIN_MIC") (class "Default")
      (node (ref "C5") (pin "1") (pinfunction "1_1") (pintype "passive"))
      (node (ref "MIC") (pin "5") (pinfunction "S_5") (pintype "passive"))
      (node (ref "R5") (pin "2") (pinfunction "2_2") (pintype "passive"))
    )
    (net (code "17") (name "EL_MIC") (class "Default")
      (node (ref "C4") (pin "1") (pinfunction "1_1") (pintype "passive"))
      (node (ref "MIC") (pin "1") (pinfunction "S_1") (pintype "passive"))
      (node (ref "R4") (pin "1") (pinfunction "1_1") (pintype "passive"))
    )
    (net (code "18") (name "GAIN_CS") (class "Default")
      (node (ref "POTI") (pin "17") (pinfunction "17_17") (pintype "passive"))
      (node (ref "POTI") (pin "18") (pinfunction "18_18") (pintype "passive"))
      (node (ref "R12") (pin "2") (pinfunction "2_2") (pintype "passive"))
    )
    (net (code "19") (name "GAIN_MAX") (class "Default")
      (node (ref "POTI") (pin "15") (pinfunction "15_15") (pintype "passive"))
      (node (ref "POTI") (pin "16") (pinfunction "16_16") (pintype "passive"))
      (node (ref "R15") (pin "2") (pinfunction "2_2") (pintype "passive"))
    )
    (net (code "20") (name "GAIN_MIN") (class "Default")
      (node (ref "C11") (pin "2") (pinfunction "2_2") (pintype "passive"))
      (node (ref "C8") (pin "1") (pinfunction "1_1") (pintype "passive"))
      (node (ref "IC1") (pin "1") (pinfunction "OUT_1") (pintype "output"))
      (node (ref "POTI") (pin "19") (pinfunction "19_19") (pintype "passive"))
      (node (ref "POTI") (pin "20") (pinfunction "20_20") (pintype "passive"))
    )
    (net (code "21") (name "GND") (class "Default")
      (node (ref "C23") (pin "2") (pinfunction "2_2") (pintype "passive"))
      (node (ref "C24") (pin "2") (pinfunction "2_2") (pintype "passive"))
      (node (ref "C25") (pin "2") (pinfunction "2_2") (pintype "passive"))
      (node (ref "C29") (pin "2") (pinfunction "2_2") (pintype "passive"))
      (node (ref "C52") (pin "2") (pinfunction "2_2") (pintype "passive"))
      (node (ref "C53") (pin "-") (pinfunction "-_-") (pintype "passive"))
      (node (ref "D14") (pin "2") (pinfunction "A_2") (pintype "passive"))
      (node (ref "IC9") (pin "2") (pinfunction "GND_2") (pintype "passive"))
      (node (ref "JP2") (pin "1") (pinfunction "1_1") (pintype "passive"))
      (node (ref "PROG") (pin "1") (pinfunction "1_1") (pintype "passive"))
      (node (ref "R48") (pin "1") (pinfunction "1_1") (pintype "passive"))
      (node (ref "SJ6") (pin "2") (pinfunction "2_2") (pintype "passive"))
      (node (ref "TAP") (pin "15") (pinfunction "15_15") (pintype "passive"))
      (node (ref "TAP") (pin "16") (pinfunction "16_16") (pintype "passive"))
      (node (ref "TAP") (pin "17") (pinfunction "17_17") (pintype "passive"))
      (node (ref "TAP") (pin "18") (pinfunction "18_18") (pintype "passive"))
      (node (ref "TAP") (pin "19") (pinfunction "19_19") (pintype "passive"))
      (node (ref "TAP") (pin "20") (pinfunction "20_20") (pintype "passive"))
    )
    (net (code "22") (name "HP") (class "Default")
      (node (ref "IC3") (pin "13") (pinfunction "X1_13") (pintype "bidirectional"))
      (node (ref "MUSOR/NORMAL") (pin "1") (pinfunction "1_1") (pintype "passive"))
      (node (ref "POTI") (pin "11") (pinfunction "11_11") (pintype "passive"))
      (node (ref "POTI") (pin "12") (pinfunction "12_12") (pintype "passive"))
    )
    (net (code "23") (name "HPOUT") (class "Default")
      (node (ref "C61") (pin "2") (pinfunction "2_2") (pintype "passive"))
      (node (ref "IC11") (pin "22") (pinfunction "LOUT_22") (pintype "output"))
      (node (ref "L12") (pin "2") (pinfunction "2_2") (pintype "passive"))
    )
    (net (code "24") (name "IN+") (class "Default")
      (node (ref "C2") (pin "1") (pinfunction "1_1") (pintype "passive"))
      (node (ref "DSUB1") (pin "2") (pinfunction "M_2") (pintype "passive"))
      (node (ref "R2") (pin "2") (pinfunction "2_2") (pintype "passive"))
      (node (ref "RJ2") (pin "2") (pinfunction "2_2") (pintype "passive"))
    )
    (net (code "25") (name "IN-") (class "Default")
      (node (ref "C3") (pin "1") (pinfunction "1_1") (pintype "passive"))
      (node (ref "DSUB1") (pin "3") (pinfunction "M_3") (pintype "passive"))
      (node (ref "R3") (pin "2") (pinfunction "2_2") (pintype "passive"))
      (node (ref "RJ2") (pin "1") (pinfunction "1_1") (pintype "passive"))
    )
    (net (code "26") (name "LAMPA_CS") (class "Default")
      (node (ref "POTI") (pin "2") (pinfunction "2_2") (pintype "passive"))
      (node (ref "T2") (pin "1") (pinfunction "B_1") (pintype "passive"))
    )
    (net (code "27") (name "LAMPA_MAX") (class "Default")
      (node (ref "D17") (pin "P$2") (pinfunction "C_P$2") (pintype "passive"))
      (node (ref "D8") (pin "2") (pinfunction "C_2") (pintype "passive"))
      (node (ref "POTI") (pin "3") (pinfunction "3_3") (pintype "passive"))
      (node (ref "R48") (pin "2") (pinfunction "2_2") (pintype "passive"))
    )
    (net (code "28") (name "LAMPA_MIN") (class "Default")
      (node (ref "POTI") (pin "1") (pinfunction "1_1") (pintype "passive"))
      (node (ref "R49") (pin "1") (pinfunction "1_1") (pintype "passive"))
    )
    (net (code "29") (name "MH") (class "Default")
      (node (ref "DIGIT") (pin "7") (pinfunction "7_7") (pintype "passive"))
      (node (ref "DIGIT") (pin "8") (pinfunction "8_8") (pintype "passive"))
      (node (ref "IC3") (pin "11") (pinfunction "A_11") (pintype "input"))
    )
    (net (code "30") (name "MIC_MUTE") (class "Default")
      (node (ref "D4") (pin "P$1") (pinfunction "A_P$1") (pintype "passive"))
      (node (ref "D9") (pin "1") (pinfunction "A_1") (pintype "passive"))
      (node (ref "DIGIT") (pin "11") (pinfunction "11_11") (pintype "passive"))
      (node (ref "DIGIT") (pin "12") (pinfunction "12_12") (pintype "passive"))
      (node (ref "SJ9") (pin "3") (pinfunction "1_3") (pintype "passive"))
    )
    (net (code "31") (name "MUTE") (class "Default")
      (node (ref "DIGIT") (pin "10") (pinfunction "10_10") (pintype "passive"))
      (node (ref "DIGIT") (pin "9") (pinfunction "9_9") (pintype "passive"))
      (node (ref "Q3") (pin "1") (pinfunction "G_1") (pintype "passive"))
    )
    (net (code "32") (name "N$49") (class "Default")
      (node (ref "IC3") (pin "14") (pinfunction "X_14") (pintype "bidirectional"))
      (node (ref "MUSOR/NORMAL") (pin "2") (pinfunction "2_2") (pintype "passive"))
      (node (ref "R30") (pin "2") (pinfunction "2_2") (pintype "passive"))
      (node (ref "SJ5") (pin "2") (pinfunction "2_2") (pintype "passive"))
    )
    (net (code "33") (name "N$50") (class "Default")
      (node (ref "IC3") (pin "15") (pinfunction "Y_15") (pintype "bidirectional"))
      (node (ref "R28") (pin "2") (pinfunction "2_2") (pintype "passive"))
      (node (ref "SJ4") (pin "2") (pinfunction "2_2") (pintype "passive"))
    )
    (net (code "34") (name "Net-(C1-Pad+)") (class "Default")
      (node (ref "C1") (pin "+") (pinfunction "+_+") (pintype "passive"))
      (node (ref "R1") (pin "1") (pinfunction "1_1") (pintype "passive"))
      (node (ref "R4") (pin "2") (pinfunction "2_2") (pintype "passive"))
    )
    (net (code "35") (name "Net-(C2-Pad2)") (class "Default")
      (node (ref "C2") (pin "2") (pinfunction "2_2") (pintype "passive"))
      (node (ref "R6") (pin "1") (pinfunction "1_1") (pintype "passive"))
    )
    (net (code "36") (name "Net-(C3-Pad2)") (class "Default")
      (node (ref "C3") (pin "2") (pinfunction "2_2") (pintype "passive"))
      (node (ref "R7") (pin "1") (pinfunction "1_1") (pintype "passive"))
    )
    (net (code "37") (name "Net-(C4-Pad2)") (class "Default")
      (node (ref "C4") (pin "2") (pinfunction "2_2") (pintype "passive"))
      (node (ref "R10") (pin "1") (pinfunction "1_1") (pintype "passive"))
    )
    (net (code "38") (name "Net-(C5-Pad2)") (class "Default")
      (node (ref "C5") (pin "2") (pinfunction "2_2") (pintype "passive"))
      (node (ref "R11") (pin "1") (pinfunction "1_1") (pintype "passive"))
      (node (ref "R8") (pin "2") (pinfunction "2_2") (pintype "passive"))
    )
    (net (code "39") (name "Net-(C6-Pad2)") (class "Default")
      (node (ref "C6") (pin "2") (pinfunction "2_2") (pintype "passive"))
      (node (ref "R8") (pin "1") (pinfunction "1_1") (pintype "passive"))
    )
    (net (code "40") (name "Net-(C11-Pad1)") (class "Default")
      (node (ref "C11") (pin "1") (pinfunction "1_1") (pintype "passive"))
      (node (ref "R16") (pin "2") (pinfunction "2_2") (pintype "passive"))
      (node (ref "R18") (pin "1") (pinfunction "1_1") (pintype "passive"))
    )
    (net (code "41") (name "Net-(C12-Pad1)") (class "Default")
      (node (ref "C12") (pin "1") (pinfunction "1_1") (pintype "passive"))
      (node (ref "R19") (pin "1") (pinfunction "1_1") (pintype "passive"))
    )
    (net (code "42") (name "Net-(C13-Pad1)") (class "Default")
      (node (ref "C13") (pin "1") (pinfunction "1_1") (pintype "passive"))
      (node (ref "R17") (pin "2") (pinfunction "2_2") (pintype "passive"))
      (node (ref "R19") (pin "2") (pinfunction "2_2") (pintype "passive"))
    )
    (net (code "43") (name "Net-(C20-Pad2)") (class "Default")
      (node (ref "C20") (pin "2") (pinfunction "2_2") (pintype "passive"))
      (node (ref "R34") (pin "1") (pinfunction "1_1") (pintype "passive"))
    )
    (net (code "44") (name "Net-(C21-Pad2)") (class "Default")
      (node (ref "C21") (pin "2") (pinfunction "2_2") (pintype "passive"))
      (node (ref "R35") (pin "1") (pinfunction "1_1") (pintype "passive"))
    )
    (net (code "45") (name "Net-(C28-Pad1)") (class "Default")
      (node (ref "C28") (pin "1") (pinfunction "1_1") (pintype "passive"))
      (node (ref "R56") (pin "1") (pinfunction "1_1") (pintype "passive"))
    )
    (net (code "46") (name "Net-(C29-Pad1)") (class "Default")
      (node (ref "C29") (pin "1") (pinfunction "1_1") (pintype "passive"))
      (node (ref "CN1") (pin "1") (pinfunction "1_1") (pintype "passive"))
      (node (ref "CN1") (pin "2") (pinfunction "2_2") (pintype "passive"))
      (node (ref "R41") (pin "1") (pinfunction "1_1") (pintype "passive"))
      (node (ref "SJ9") (pin "2") (pinfunction "2_2") (pintype "passive"))
    )
    (net (code "47") (name "Net-(C63-Pad1)") (class "Default")
      (node (ref "C63") (pin "1") (pinfunction "1_1") (pintype "passive"))
      (node (ref "C65") (pin "+") (pinfunction "+_+") (pintype "passive"))
      (node (ref "L10") (pin "2") (pinfunction "2_2") (pintype "passive"))
      (node (ref "R52") (pin "2") (pinfunction "2_2") (pintype "passive"))
    )
    (net (code "48") (name "Net-(C64-Pad2)") (class "Default")
      (node (ref "C64") (pin "2") (pinfunction "2_2") (pintype "passive"))
      (node (ref "L11") (pin "2") (pinfunction "2_2") (pintype "passive"))
      (node (ref "L12") (pin "1") (pinfunction "1_1") (pintype "passive"))
      (node (ref "R53") (pin "1") (pinfunction "1_1") (pintype "passive"))
    )
    (net (code "49") (name "Net-(C66-Pad+)") (class "Default")
      (node (ref "C66") (pin "+") (pinfunction "+_+") (pintype "passive"))
      (node (ref "C70") (pin "2") (pinfunction "2_2") (pintype "passive"))
      (node (ref "L11") (pin "1") (pinfunction "1_1") (pintype "passive"))
    )
    (net (code "50") (name "Net-(C68-Pad1)") (class "Default")
      (node (ref "C68") (pin "1") (pinfunction "1_1") (pintype "passive"))
      (node (ref "SJ4") (pin "1") (pinfunction "1_1") (pintype "passive"))
    )
    (net (code "51") (name "Net-(C69-Pad1)") (class "Default")
      (node (ref "C69") (pin "1") (pinfunction "1_1") (pintype "passive"))
      (node (ref "SJ5") (pin "1") (pinfunction "1_1") (pintype "passive"))
    )
    (net (code "52") (name "Net-(C71-Pad1)") (class "Default")
      (node (ref "C71") (pin "1") (pinfunction "1_1") (pintype "passive"))
      (node (ref "R55") (pin "2") (pinfunction "2_2") (pintype "passive"))
      (node (ref "SD2") (pin "HACK") (pinfunction "HACK_HACK") (pintype "bidirectional"))
    )
    (net (code "53") (name "Net-(D1-C)") (class "Default")
      (node (ref "C12") (pin "2") (pinfunction "2_2") (pintype "passive"))
      (node (ref "D1") (pin "P$2") (pinfunction "C_P$2") (pintype "passive"))
      (node (ref "D11") (pin "2") (pinfunction "C_2") (pintype "passive"))
      (node (ref "D2") (pin "P$1") (pinfunction "A_P$1") (pintype "passive"))
      (node (ref "D20") (pin "1") (pinfunction "A_1") (pintype "passive"))
    )
    (net (code "54") (name "Net-(D4-C)") (class "Default")
      (node (ref "D4") (pin "P$2") (pinfunction "C_P$2") (pintype "passive"))
      (node (ref "D9") (pin "2") (pinfunction "C_2") (pintype "passive"))
      (node (ref "Q1") (pin "1") (pinfunction "G_1") (pintype "passive"))
      (node (ref "R38") (pin "2") (pinfunction "2_2") (pintype "passive"))
    )
    (net (code "55") (name "Net-(D10-A)") (class "Default")
      (node (ref "D10") (pin "1") (pinfunction "A_1") (pintype "passive"))
      (node (ref "D3") (pin "P$1") (pinfunction "A_P$1") (pintype "passive"))
      (node (ref "R26") (pin "2") (pinfunction "2_2") (pintype "passive"))
    )
    (net (code "56") (name "Net-(D10-C)") (class "Default")
      (node (ref "C17") (pin "1") (pinfunction "1_1") (pintype "passive"))
      (node (ref "D10") (pin "2") (pinfunction "C_2") (pintype "passive"))
      (node (ref "D3") (pin "P$2") (pinfunction "C_P$2") (pintype "passive"))
      (node (ref "R27") (pin "2") (pinfunction "2_2") (pintype "passive"))
    )
    (net (code "57") (name "Net-(D12-A)") (class "Default")
      (node (ref "D12") (pin "2") (pinfunction "A_2") (pintype "passive"))
      (node (ref "RJ2") (pin "8") (pinfunction "8_8") (pintype "passive"))
    )
    (net (code "58") (name "Net-(D13-A)") (class "Default")
      (node (ref "D13") (pin "2") (pinfunction "A_2") (pintype "passive"))
      (node (ref "DSUB1") (pin "8") (pinfunction "M_8") (pintype "passive"))
    )
    (net (code "59") (name "Net-(D14-C)") (class "Default")
      (node (ref "D14") (pin "1") (pinfunction "C_1") (pintype "passive"))
      (node (ref "JP1") (pin "1") (pinfunction "1_1") (pintype "passive"))
      (node (ref "L9") (pin "1") (pinfunction "1_1") (pintype "passive"))
    )
    (net (code "60") (name "Net-(D16-C)") (class "Default")
      (node (ref "D16") (pin "P$2") (pinfunction "C_P$2") (pintype "passive"))
      (node (ref "D17") (pin "P$1") (pinfunction "A_P$1") (pintype "passive"))
      (node (ref "D7") (pin "2") (pinfunction "C_2") (pintype "passive"))
      (node (ref "D8") (pin "1") (pinfunction "A_1") (pintype "passive"))
    )
    (net (code "61") (name "Net-(D18-A)") (class "Default")
      (node (ref "D18") (pin "P$1") (pinfunction "A_P$1") (pintype "passive"))
      (node (ref "D19") (pin "P$2") (pinfunction "C_P$2") (pintype "passive"))
      (node (ref "D5") (pin "2") (pinfunction "C_2") (pintype "passive"))
      (node (ref "D6") (pin "1") (pinfunction "A_1") (pintype "passive"))
      (node (ref "R55") (pin "1") (pinfunction "1_1") (pintype "passive"))
    )
    (net (code "62") (name "Net-(D19-A)") (class "Default")
      (node (ref "C54") (pin "-") (pinfunction "-_-") (pintype "passive"))
      (node (ref "C55") (pin "2") (pinfunction "2_2") (pintype "passive"))
      (node (ref "D15") (pin "A") (pinfunction "A_A") (pintype "passive"))
      (node (ref "D19") (pin "P$1") (pinfunction "A_P$1") (pintype "passive"))
      (node (ref "D5") (pin "1") (pinfunction "A_1") (pintype "passive"))
      (node (ref "SJ1") (pin "2") (pinfunction "2_2") (pintype "passive"))
      (node (ref "SJ7") (pin "1") (pinfunction "1_1") (pintype "passive"))
    )
    (net (code "63") (name "Net-(F2-Pad2)") (class "Default")
      (node (ref "F2") (pin "2") (pinfunction "2_2") (pintype "passive"))
      (node (ref "L7") (pin "1") (pinfunction "1_1") (pintype "passive"))
    )
    (net (code "64") (name "Net-(F_LED-Pad2)") (class "Default")
      (node (ref "F_LED") (pin "2") (pinfunction "2_2") (pintype "passive"))
      (node (ref "R27") (pin "1") (pinfunction "1_1") (pintype "passive"))
    )
    (net (code "65") (name "Net-(HP_KIB-S)") (class "Default")
      (node (ref "C28") (pin "2") (pinfunction "2_2") (pintype "passive"))
      (node (ref "C66") (pin "-") (pinfunction "-_-") (pintype "passive"))
      (node (ref "HP_KI") (pin "2") (pinfunction "S_2") (pintype "passive"))
      (node (ref "R40") (pin "1") (pinfunction "1_1") (pintype "passive"))
      (node (ref "R41") (pin "2") (pinfunction "2_2") (pintype "passive"))
      (node (ref "R42") (pin "2") (pinfunction "2_2") (pintype "passive"))
    )
    (net (code "66") (name "Net-(IC1A-+IN)") (class "Default")
      (node (ref "C10") (pin "1") (pinfunction "1_1") (pintype "passive"))
      (node (ref "IC1") (pin "3") (pinfunction "+IN_3") (pintype "input"))
      (node (ref "R10") (pin "2") (pinfunction "2_2") (pintype "passive"))
      (node (ref "R14") (pin "2") (pinfunction "2_2") (pintype "passive"))
    )
    (net (code "67") (name "Net-(IC1A--IN)") (class "Default")
      (node (ref "C6") (pin "1") (pinfunction "1_1") (pintype "passive"))
      (node (ref "C8") (pin "2") (pinfunction "2_2") (pintype "passive"))
      (node (ref "IC1") (pin "2") (pinfunction "-IN_2") (pintype "input"))
      (node (ref "R11") (pin "2") (pinfunction "2_2") (pintype "passive"))
      (node (ref "R12") (pin "1") (pinfunction "1_1") (pintype "passive"))
    )
    (net (code "68") (name "Net-(IC1B-+IN)") (class "Default")
      (node (ref "FENYELL") (pin "2") (pinfunction "2_2") (pintype "passive"))
      (node (ref "IC1") (pin "5") (pinfunction "+IN_5") (pintype "input"))
      (node (ref "Q1") (pin "3") (pinfunction "D_3") (pintype "passive"))
      (node (ref "R18") (pin "2") (pinfunction "2_2") (pintype "passive"))
    )
    (net (code "69") (name "Net-(IC1B--IN)") (class "Default")
      (node (ref "C14") (pin "2") (pinfunction "2_2") (pintype "passive"))
      (node (ref "IC1") (pin "6") (pinfunction "-IN_6") (pintype "input"))
      (node (ref "R20") (pin "2") (pinfunction "2_2") (pintype "passive"))
      (node (ref "R21") (pin "1") (pinfunction "1_1") (pintype "passive"))
    )
    (net (code "70") (name "Net-(IC1B-OUT)") (class "Default")
      (node (ref "C14") (pin "1") (pinfunction "1_1") (pintype "passive"))
      (node (ref "C15") (pin "2") (pinfunction "2_2") (pintype "passive"))
      (node (ref "IC1") (pin "7") (pinfunction "OUT_7") (pintype "output"))
      (node (ref "IC2") (pin "3") (pinfunction "+IN_3") (pintype "input"))
      (node (ref "R21") (pin "2") (pinfunction "2_2") (pintype "passive"))
    )
    (net (code "71") (name "Net-(IC2A--IN)") (class "Default")
      (node (ref "C16") (pin "2") (pinfunction "2_2") (pintype "passive"))
      (node (ref "IC2") (pin "2") (pinfunction "-IN_2") (pintype "input"))
      (node (ref "R22") (pin "2") (pinfunction "2_2") (pintype "passive"))
      (node (ref "R23") (pin "1") (pinfunction "1_1") (pintype "passive"))
    )
    (net (code "72") (name "Net-(IC2A-OUT)") (class "Default")
      (node (ref "C16") (pin "1") (pinfunction "1_1") (pintype "passive"))
      (node (ref "IC2") (pin "1") (pinfunction "OUT_1") (pintype "output"))
      (node (ref "LED1") (pin "K") (pinfunction "C_K") (pintype "passive"))
      (node (ref "R25") (pin "2") (pinfunction "2_2") (pintype "passive"))
      (node (ref "R26") (pin "1") (pinfunction "1_1") (pintype "passive"))
    )
    (net (code "73") (name "Net-(IC2B-+IN)") (class "Default")
      (node (ref "C7") (pin "1") (pinfunction "1_1") (pintype "passive"))
      (node (ref "IC2") (pin "5") (pinfunction "+IN_5") (pintype "input"))
      (node (ref "R6") (pin "2") (pinfunction "2_2") (pintype "passive"))
      (node (ref "R9") (pin "2") (pinfunction "2_2") (pintype "passive"))
    )
    (net (code "74") (name "Net-(IC2B--IN)") (class "Default")
      (node (ref "C9") (pin "2") (pinfunction "2_2") (pintype "passive"))
      (node (ref "IC2") (pin "6") (pinfunction "-IN_6") (pintype "input"))
      (node (ref "R13") (pin "1") (pinfunction "1_1") (pintype "passive"))
      (node (ref "R7") (pin "2") (pinfunction "2_2") (pintype "passive"))
    )
    (net (code "75") (name "Net-(IC2B-OUT)") (class "Default")
      (node (ref "C9") (pin "1") (pinfunction "1_1") (pintype "passive"))
      (node (ref "IC2") (pin "7") (pinfunction "OUT_7") (pintype "output"))
      (node (ref "R13") (pin "2") (pinfunction "2_2") (pintype "passive"))
      (node (ref "R17") (pin "1") (pinfunction "1_1") (pintype "passive"))
    )
    (net (code "76") (name "Net-(IC3A-INH)") (class "Default")
      (node (ref "IC3") (pin "6") (pinfunction "INH_6") (pintype "input"))
      (node (ref "Q3") (pin "3") (pinfunction "D_3") (pintype "passive"))
      (node (ref "R54") (pin "1") (pinfunction "1_1") (pintype "passive"))
    )
    (net (code "77") (name "Net-(IC3A-Y0)") (class "Default")
      (node (ref "IC3") (pin "2") (pinfunction "Y0_2") (pintype "bidirectional"))
      (node (ref "IC3") (pin "4") (pinfunction "Z_4") (pintype "bidirectional"))
    )
    (net (code "78") (name "Net-(IC4A-+IN)") (class "Default")
      (node (ref "C15") (pin "1") (pinfunction "1_1") (pintype "passive"))
      (node (ref "IC4") (pin "3") (pinfunction "+IN_3") (pintype "input"))
      (node (ref "R24") (pin "2") (pinfunction "2_2") (pintype "passive"))
      (node (ref "R29") (pin "2") (pinfunction "2_2") (pintype "passive"))
    )
    (net (code "79") (name "Net-(IC4A--IN)") (class "Default")
      (node (ref "C18") (pin "2") (pinfunction "2_2") (pintype "passive"))
      (node (ref "IC4") (pin "2") (pinfunction "-IN_2") (pintype "input"))
      (node (ref "R31") (pin "2") (pinfunction "2_2") (pintype "passive"))
      (node (ref "R32") (pin "1") (pinfunction "1_1") (pintype "passive"))
    )
    (net (code "80") (name "Net-(IC4A-OUT)") (class "Default")
      (node (ref "C18") (pin "1") (pinfunction "1_1") (pintype "passive"))
      (node (ref "C20") (pin "1") (pinfunction "1_1") (pintype "passive"))
      (node (ref "IC4") (pin "1") (pinfunction "OUT_1") (pintype "output"))
      (node (ref "R32") (pin "2") (pinfunction "2_2") (pintype "passive"))
    )
    (net (code "81") (name "Net-(IC4B--IN)") (class "Default")
      (node (ref "C19") (pin "2") (pinfunction "2_2") (pintype "passive"))
      (node (ref "IC4") (pin "6") (pinfunction "-IN_6") (pintype "input"))
      (node (ref "R29") (pin "1") (pinfunction "1_1") (pintype "passive"))
      (node (ref "R33") (pin "1") (pinfunction "1_1") (pintype "passive"))
    )
    (net (code "82") (name "Net-(IC4B-OUT)") (class "Default")
      (node (ref "C19") (pin "1") (pinfunction "1_1") (pintype "passive"))
      (node (ref "C21") (pin "1") (pinfunction "1_1") (pintype "passive"))
      (node (ref "IC4") (pin "7") (pinfunction "OUT_7") (pintype "output"))
      (node (ref "R33") (pin "2") (pinfunction "2_2") (pintype "passive"))
    )
    (net (code "83") (name "Net-(IC11-BSL)") (class "Default")
      (node (ref "C61") (pin "1") (pinfunction "1_1") (pintype "passive"))
      (node (ref "IC11") (pin "21") (pinfunction "BSL_21") (pintype "passive"))
    )
    (net (code "84") (name "Net-(IC11-BSR)") (class "Default")
      (node (ref "C60") (pin "1") (pinfunction "1_1") (pintype "passive"))
      (node (ref "IC11") (pin "16") (pinfunction "BSR_16") (pintype "passive"))
    )
    (net (code "85") (name "Net-(IC11-BYPASS)") (class "Default")
      (node (ref "C56") (pin "1") (pinfunction "1_1") (pintype "passive"))
      (node (ref "IC11") (pin "7") (pinfunction "BYPASS_7") (pintype "input"))
      (node (ref "R39") (pin "1") (pinfunction "1_1") (pintype "passive"))
    )
    (net (code "86") (name "Net-(IC11-GAIN0)") (class "Default")
      (node (ref "IC11") (pin "18") (pinfunction "GAIN0_18") (pintype "input"))
      (node (ref "SJ2") (pin "2") (pinfunction "2_2") (pintype "passive"))
    )
    (net (code "87") (name "Net-(IC11-LIN)") (class "Default")
      (node (ref "C69") (pin "2") (pinfunction "2_2") (pintype "passive"))
      (node (ref "IC11") (pin "5") (pinfunction "LIN_5") (pintype "input"))
    )
    (net (code "88") (name "Net-(IC11-MUTE)") (class "Default")
      (node (ref "IC11") (pin "4") (pinfunction "MUTE_4") (pintype "input"))
      (node (ref "SJ8") (pin "1") (pinfunction "1_1") (pintype "passive"))
    )
    (net (code "89") (name "Net-(IC11-RIN)") (class "Default")
      (node (ref "C68") (pin "2") (pinfunction "2_2") (pintype "passive"))
      (node (ref "IC11") (pin "6") (pinfunction "RIN_6") (pintype "input"))
    )
    (net (code "90") (name "Net-(IC11-VCLAMP)") (class "Default")
      (node (ref "C59") (pin "1") (pinfunction "1_1") (pintype "passive"))
      (node (ref "IC11") (pin "11") (pinfunction "VCLAMP_11") (pintype "input"))
    )
    (net (code "91") (name "Net-(LAMPAB-S)") (class "Default")
      (node (ref "LAMPA") (pin "2") (pinfunction "S_2") (pintype "passive"))
      (node (ref "T2") (pin "2") (pinfunction "C_2") (pintype "passive"))
    )
    (net (code "92") (name "Net-(LED1-PadA)") (class "Default")
      (node (ref "LED1") (pin "A") (pinfunction "A_A") (pintype "passive"))
      (node (ref "R23") (pin "2") (pinfunction "2_2") (pintype "passive"))
      (node (ref "R25") (pin "1") (pinfunction "1_1") (pintype "passive"))
    )
    (net (code "93") (name "Net-(PROG-Pad4)") (class "Default")
      (node (ref "PROG") (pin "4") (pinfunction "4_4") (pintype "passive"))
      (node (ref "R36") (pin "2") (pinfunction "2_2") (pintype "passive"))
    )
    (net (code "94") (name "Net-(PROG-Pad8)") (class "Default")
      (node (ref "PROG") (pin "8") (pinfunction "8_8") (pintype "passive"))
      (node (ref "R37") (pin "2") (pinfunction "2_2") (pintype "passive"))
    )
    (net (code "95") (name "Net-(SD2-CTRL)") (class "Default")
      (node (ref "C48") (pin "1") (pinfunction "1_1") (pintype "passive"))
      (node (ref "C49") (pin "+") (pinfunction "+_+") (pintype "passive"))
      (node (ref "R47") (pin "2") (pinfunction "2_2") (pintype "passive"))
      (node (ref "SD2") (pin "CONTROL") (pinfunction "CTRL_CONTROL") (pintype "bidirectional"))
    )
    (net (code "96") (name "Net-(SD2-IN+)") (class "Default")
      (node (ref "C22") (pin "+") (pinfunction "+_+") (pintype "passive"))
      (node (ref "C47") (pin "+") (pinfunction "+_+") (pintype "passive"))
      (node (ref "L7") (pin "2") (pinfunction "2_2") (pintype "passive"))
      (node (ref "SD2") (pin "INPUT+") (pinfunction "IN+_INPUT+") (pintype "bidirectional"))
    )
    (net (code "97") (name "Net-(SD2-IN-)") (class "Default")
      (node (ref "C22") (pin "-") (pinfunction "-_-") (pintype "passive"))
      (node (ref "C47") (pin "-") (pinfunction "-_-") (pintype "passive"))
      (node (ref "C48") (pin "2") (pinfunction "2_2") (pintype "passive"))
      (node (ref "C49") (pin "-") (pinfunction "-_-") (pintype "passive"))
      (node (ref "L8") (pin "2") (pinfunction "2_2") (pintype "passive"))
      (node (ref "R47") (pin "1") (pinfunction "1_1") (pintype "passive"))
      (node (ref "SD2") (pin "INPUT-") (pinfunction "IN-_INPUT-") (pintype "bidirectional"))
    )
    (net (code "98") (name "Net-(SD2-PadOUT-)") (class "Default")
      (node (ref "SD2") (pin "OUT-") (pinfunction "OUT-_OUT-") (pintype "bidirectional"))
      (node (ref "SJ7") (pin "2") (pinfunction "2_2") (pintype "passive"))
    )
    (net (code "99") (name "Net-(SP_KIB-S)") (class "Default")
      (node (ref "C65") (pin "-") (pinfunction "-_-") (pintype "passive"))
      (node (ref "SP_KI") (pin "2") (pinfunction "S_2") (pintype "passive"))
    )
    (net (code "100") (name "Net-(T2-E)") (class "Default")
      (node (ref "R50") (pin "1") (pinfunction "1_1") (pintype "passive"))
      (node (ref "T2") (pin "3") (pinfunction "E_3") (pintype "passive"))
    )
    (net (code "101") (name "OUT+") (class "Default")
      (node (ref "DSUB1") (pin "4") (pinfunction "M_4") (pintype "passive"))
      (node (ref "R34") (pin "2") (pinfunction "2_2") (pintype "passive"))
      (node (ref "RJ2") (pin "6") (pinfunction "6_6") (pintype "passive"))
    )
    (net (code "102") (name "OUT-") (class "Default")
      (node (ref "DSUB1") (pin "5") (pinfunction "M_5") (pintype "passive"))
      (node (ref "R35") (pin "2") (pinfunction "2_2") (pintype "passive"))
      (node (ref "RJ2") (pin "3") (pinfunction "3_3") (pintype "passive"))
    )
    (net (code "103") (name "POTI_JEL") (class "Default")
      (node (ref "C13") (pin "2") (pinfunction "2_2") (pintype "passive"))
      (node (ref "POTI") (pin "7") (pinfunction "7_7") (pintype "passive"))
      (node (ref "POTI") (pin "8") (pinfunction "8_8") (pintype "passive"))
    )
    (net (code "104") (name "SP") (class "Default")
      (node (ref "MUSOR/NORMAL") (pin "5") (pinfunction "5_5") (pintype "passive"))
      (node (ref "POTI") (pin "10") (pinfunction "10_10") (pintype "passive"))
      (node (ref "POTI") (pin "9") (pinfunction "9_9") (pintype "passive"))
    )
    (net (code "105") (name "SPM") (class "Default")
      (node (ref "DIGIT") (pin "5") (pinfunction "5_5") (pintype "passive"))
      (node (ref "DIGIT") (pin "6") (pinfunction "6_6") (pintype "passive"))
      (node (ref "IC3") (pin "10") (pinfunction "B_10") (pintype "input"))
    )
    (net (code "106") (name "SPOUT") (class "Default")
      (node (ref "C60") (pin "2") (pinfunction "2_2") (pintype "passive"))
      (node (ref "C71") (pin "2") (pinfunction "2_2") (pintype "passive"))
      (node (ref "IC11") (pin "15") (pinfunction "ROUT_15") (pintype "output"))
      (node (ref "L10") (pin "1") (pinfunction "1_1") (pintype "passive"))
    )
    (net (code "107") (name "VDD") (class "Default")
      (node (ref "C26") (pin "1") (pinfunction "1_1") (pintype "passive"))
      (node (ref "C57") (pin "+") (pinfunction "+_+") (pintype "passive"))
      (node (ref "C58") (pin "1") (pinfunction "1_1") (pintype "passive"))
      (node (ref "IC1") (pin "8") (pinfunction "V+_8") (pintype "power_in"))
      (node (ref "IC11") (pin "19") (pinfunction "AVCC_19") (pintype "input"))
      (node (ref "IC11") (pin "20") (pinfunction "AVCC_20") (pintype "input"))
      (node (ref "IC2") (pin "8") (pinfunction "V+_8") (pintype "power_in"))
      (node (ref "IC4") (pin "8") (pinfunction "V+_8") (pintype "power_in"))
      (node (ref "R1") (pin "2") (pinfunction "2_2") (pintype "passive"))
      (node (ref "R39") (pin "2") (pinfunction "2_2") (pintype "passive"))
      (node (ref "R51") (pin "1") (pinfunction "1_1") (pintype "passive"))
      (node (ref "SJ2") (pin "1") (pinfunction "1_1") (pintype "passive"))
    )
    (net (code "108") (name "VSS") (class "Default")
      (node (ref "C27") (pin "2") (pinfunction "2_2") (pintype "passive"))
      (node (ref "IC1") (pin "4") (pinfunction "V-_4") (pintype "power_in"))
      (node (ref "IC2") (pin "4") (pinfunction "V-_4") (pintype "power_in"))
      (node (ref "IC3") (pin "7") (pinfunction "VEE_7") (pintype "power_in"))
      (node (ref "IC4") (pin "4") (pinfunction "V-_4") (pintype "power_in"))
      (node (ref "SJ1") (pin "1") (pinfunction "1_1") (pintype "passive"))
    )
    (net (code "109") (name "X0") (class "Default")
      (node (ref "IC3") (pin "12") (pinfunction "X0_12") (pintype "bidirectional"))
      (node (ref "MUSOR/NORMAL") (pin "3") (pinfunction "3_3") (pintype "passive"))
    )
    (net (code "110") (name "unconnected-(IC12-GND-Pad2)") (class "Default")
      (node (ref "IC12") (pin "2") (pinfunction "GND_2") (pintype "passive"))
    )
    (net (code "111") (name "unconnected-(IC12-VI-Pad1)") (class "Default")
      (node (ref "IC12") (pin "1") (pinfunction "VI_1") (pintype "input"))
    )
    (net (code "112") (name "unconnected-(IC12-VO-Pad3)") (class "Default")
      (node (ref "IC12") (pin "3") (pinfunction "VO_3") (pintype "passive"))
    )
    (net (code "113") (name "unconnected-(POTI-Pad4)") (class "Default")
      (node (ref "POTI") (pin "4") (pinfunction "4_4") (pintype "passive"))
    )
    (net (code "114") (name "unconnected-(SD2-PadSZAB)") (class "Default")
      (node (ref "SD2") (pin "SZAB") (pinfunction "SZAB_SZAB") (pintype "bidirectional"))
    )
  )
)
